# OBI_SlaveBoard_rev3.net
KiCad netlist of a schematic drawn in EAGLE
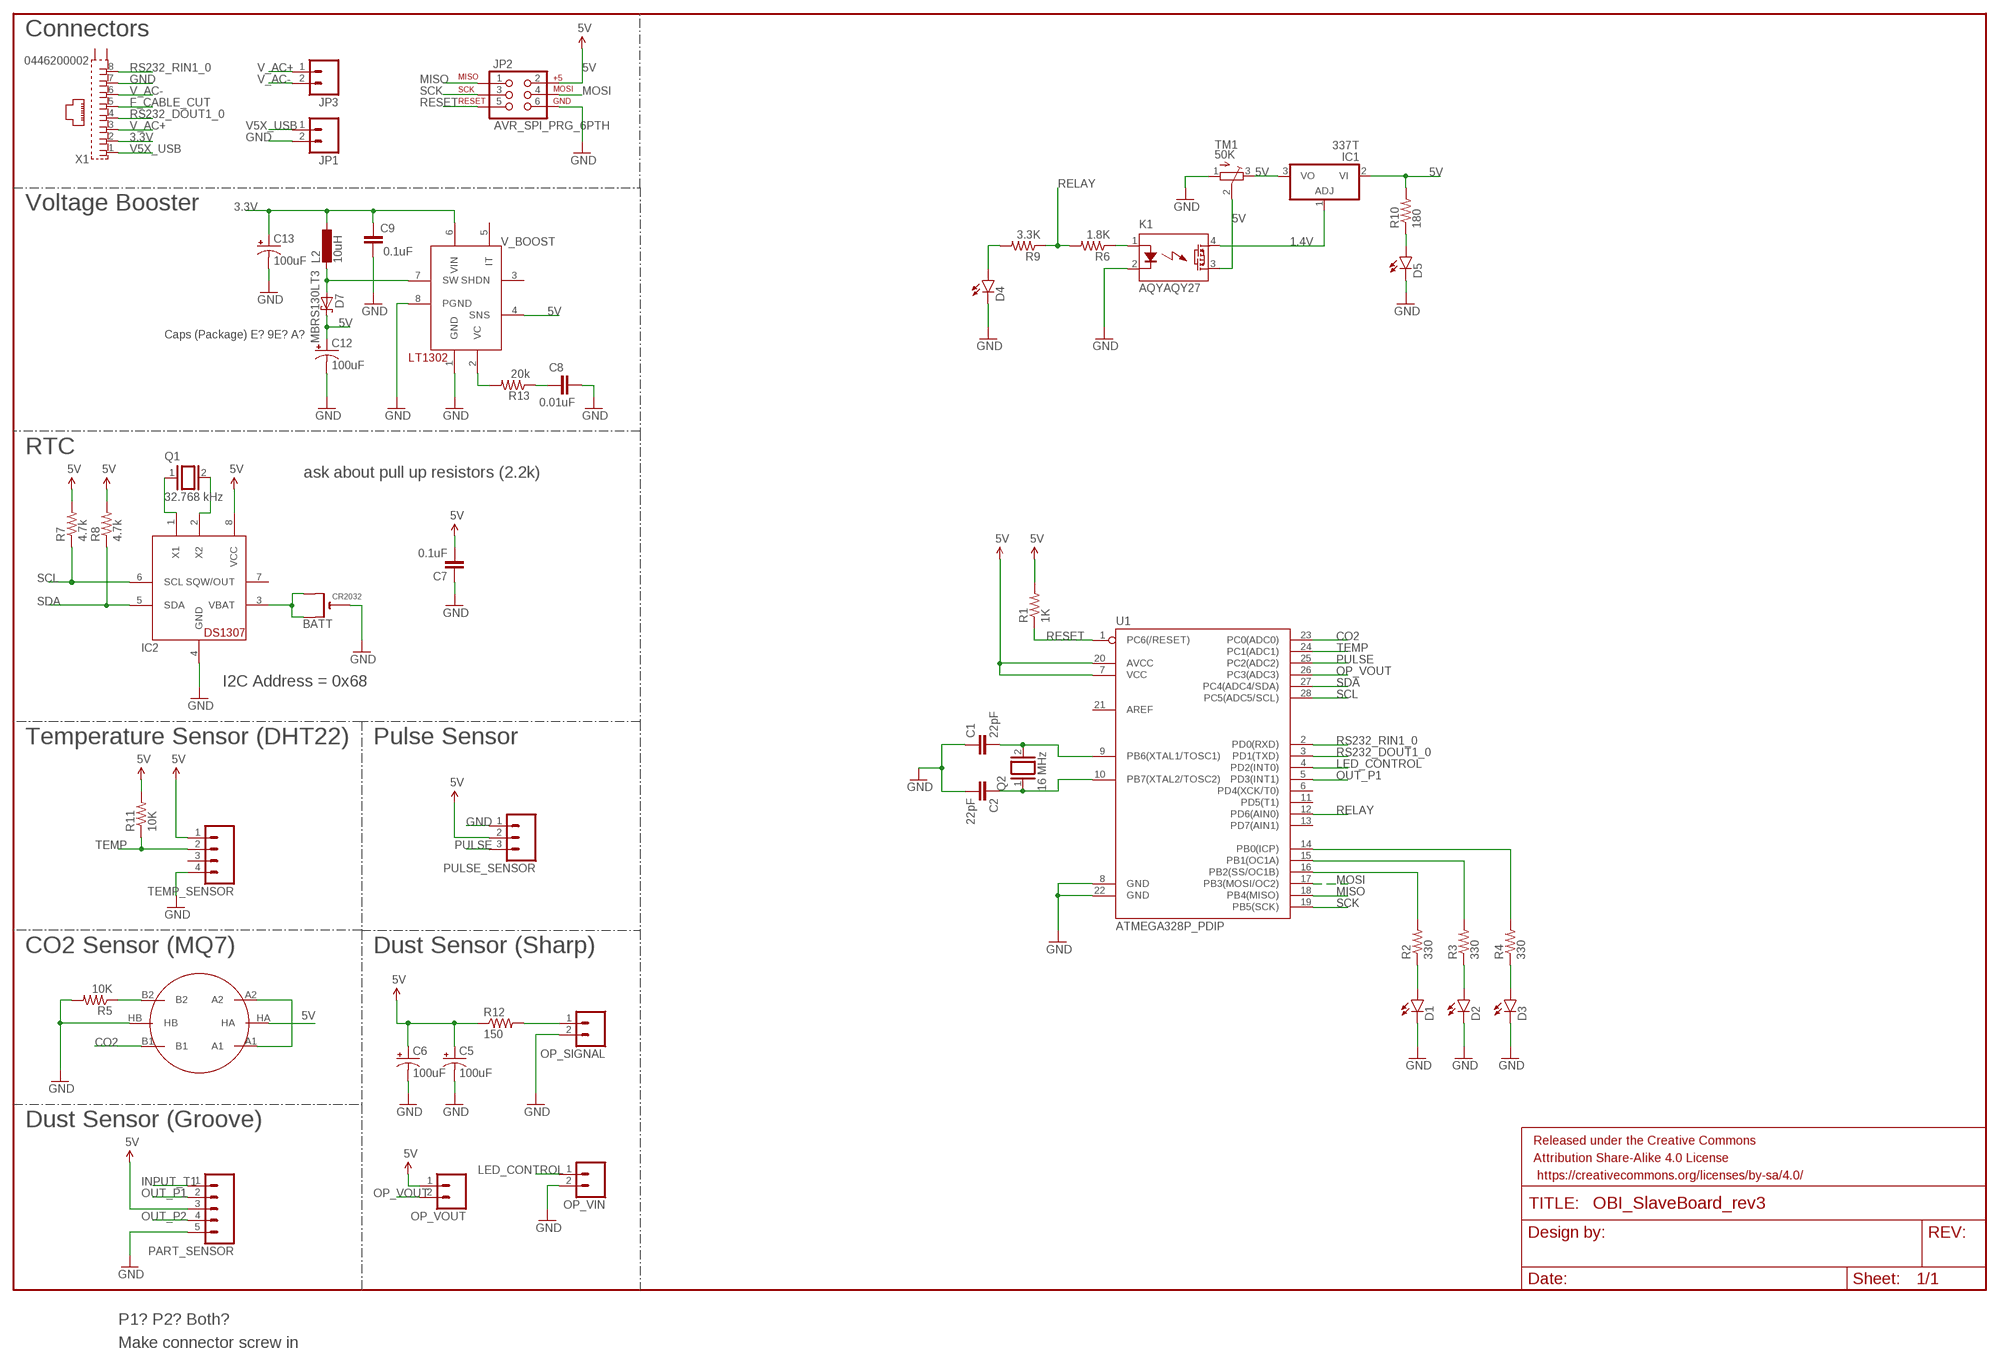
[diagram p0: schematic, sheet 1]

(export (version "E")
  (design (tool "Eeschema 10.0.6"))
  (components
    (comp (ref "BATT")
      (value "CR2032THM")
      (footprint "eagle-import:CR2032-THRU")
      (libsource (lib "eagle-import") (part "CR2032THM"))
    )
    (comp (ref "C1")
      (value "22pF")
      (footprint "eagle-import:CAP-PTH-SMALL-KIT")
      (libsource (lib "eagle-import") (part "CAPKIT"))
    )
    (comp (ref "C2")
      (value "22pF")
      (footprint "eagle-import:CAP-PTH-SMALL-KIT")
      (libsource (lib "eagle-import") (part "CAPKIT"))
    )
    (comp (ref "C5")
      (value "100uF")
      (footprint "eagle-import:CPOL-RADIAL-10UF-25V")
      (libsource (lib "eagle-import") (part "CAP_POLPTH2"))
    )
    (comp (ref "C6")
      (value "100uF")
      (footprint "eagle-import:CPOL-RADIAL-10UF-25V")
      (libsource (lib "eagle-import") (part "CAP_POLPTH2"))
    )
    (comp (ref "C7")
      (value "0.1uF")
      (footprint "eagle-import:CAP-PTH-SMALL-KIT")
      (libsource (lib "eagle-import") (part "CAPKIT"))
    )
    (comp (ref "C8")
      (value "0.01uF")
      (footprint "eagle-import:CAP-PTH-SMALL-KIT")
      (libsource (lib "eagle-import") (part "CAPKIT"))
    )
    (comp (ref "C9")
      (value "0.1uF")
      (footprint "eagle-import:CAP-PTH-SMALL-KIT")
      (libsource (lib "eagle-import") (part "CAPKIT"))
    )
    (comp (ref "C12")
      (value "100uF")
      (footprint "eagle-import:SANYO-OSCON_9E")
      (libsource (lib "eagle-import") (part "CPOL-USSANYO_9E"))
    )
    (comp (ref "C13")
      (value "100uF")
      (footprint "eagle-import:SANYO-OSCON_9E")
      (libsource (lib "eagle-import") (part "CPOL-USSANYO_9E"))
    )
    (comp (ref "CO2_SENSOR")
      (value "METHANE_SENSOR")
      (footprint "eagle-import:MQ-3")
      (libsource (lib "eagle-import") (part "METHANE_SENSOR"))
    )
    (comp (ref "D1")
      (value "LED5MM")
      (footprint "eagle-import:LED5MM")
      (libsource (lib "eagle-import") (part "LED5MM"))
    )
    (comp (ref "D2")
      (value "LED5MM")
      (footprint "eagle-import:LED5MM")
      (libsource (lib "eagle-import") (part "LED5MM"))
    )
    (comp (ref "D3")
      (value "LED5MM")
      (footprint "eagle-import:LED5MM")
      (libsource (lib "eagle-import") (part "LED5MM"))
    )
    (comp (ref "D4")
      (value "LED5MM")
      (footprint "eagle-import:LED5MM")
      (libsource (lib "eagle-import") (part "LED5MM"))
    )
    (comp (ref "D5")
      (value "LED5MM")
      (footprint "eagle-import:LED5MM")
      (libsource (lib "eagle-import") (part "LED5MM"))
    )
    (comp (ref "D7")
      (value "MBRS130LT3")
      (footprint "eagle-import:SMB")
      (libsource (lib "eagle-import") (part "MBRS130LT3"))
    )
    (comp (ref "FRAME1")
      (value "FRAME-LEDGER")
      (footprint "eagle-import:CREATIVE_COMMONS")
      (libsource (lib "eagle-import") (part "FRAME-LEDGER"))
    )
    (comp (ref "IC1")
      (value "337T")
      (footprint "eagle-import:TO220H")
      (libsource (lib "eagle-import") (part "337T"))
    )
    (comp (ref "IC2")
      (value "DS1307")
      (footprint "eagle-import:DIL08")
      (libsource (lib "eagle-import") (part "DS1307"))
    )
    (comp (ref "JP1")
      (value "M023.5MM")
      (footprint "eagle-import:SCREWTERMINAL-3.5MM-2")
      (libsource (lib "eagle-import") (part "M023.5MM"))
    )
    (comp (ref "JP2")
      (value "AVR_SPI_PRG_6PTH")
      (footprint "eagle-import:2X3")
      (libsource (lib "eagle-import") (part "AVR_SPI_PRG_6PTH"))
    )
    (comp (ref "JP3")
      (value "M023.5MM")
      (footprint "eagle-import:SCREWTERMINAL-3.5MM-2")
      (libsource (lib "eagle-import") (part "M023.5MM"))
    )
    (comp (ref "K1")
      (value "AQYAQY27")
      (footprint "eagle-import:AQY27")
      (libsource (lib "eagle-import") (part "AQYAQY27"))
    )
    (comp (ref "L2")
      (value "10uH")
      (footprint "eagle-import:DO3316P")
      (libsource (lib "eagle-import") (part "DO3316P"))
    )
    (comp (ref "OP_SIGNAL")
      (value "M023.5MM")
      (footprint "eagle-import:SCREWTERMINAL-3.5MM-2")
      (libsource (lib "eagle-import") (part "M023.5MM"))
    )
    (comp (ref "OP_VIN")
      (value "M023.5MM")
      (footprint "eagle-import:SCREWTERMINAL-3.5MM-2")
      (libsource (lib "eagle-import") (part "M023.5MM"))
    )
    (comp (ref "OP_VOUT")
      (value "M023.5MM")
      (footprint "eagle-import:SCREWTERMINAL-3.5MM-2")
      (libsource (lib "eagle-import") (part "M023.5MM"))
    )
    (comp (ref "PART_SENSOR")
      (value "M05JST")
      (footprint "eagle-import:JST-5-PTH")
      (libsource (lib "eagle-import") (part "M05JST"))
    )
    (comp (ref "PULSE_SENSOR")
      (value "M03-SCREW-5MM")
      (footprint "eagle-import:SCREWTERMINAL-5MM-3")
      (libsource (lib "eagle-import") (part "M03-SCREW-5MM"))
    )
    (comp (ref "Q1")
      (value "32.768 kHz")
      (footprint "eagle-import:QS")
      (libsource (lib "eagle-import") (part "XTAL/S"))
    )
    (comp (ref "Q2")
      (value "16 MHz")
      (footprint "eagle-import:QS")
      (libsource (lib "eagle-import") (part "XTAL/S"))
    )
    (comp (ref "R1")
      (value "1K")
      (footprint "eagle-import:AXIAL-0.4")
      (libsource (lib "eagle-import") (part "RESISTORPTH-1/4W"))
    )
    (comp (ref "R2")
      (value "330")
      (footprint "eagle-import:AXIAL-0.4")
      (libsource (lib "eagle-import") (part "SparkFun-Resistors_RESISTORPTH-1/4W"))
    )
    (comp (ref "R3")
      (value "330")
      (footprint "eagle-import:AXIAL-0.4")
      (libsource (lib "eagle-import") (part "SparkFun-Resistors_RESISTORPTH-1/4W"))
    )
    (comp (ref "R4")
      (value "330")
      (footprint "eagle-import:AXIAL-0.4")
      (libsource (lib "eagle-import") (part "SparkFun-Resistors_RESISTORPTH-1/4W"))
    )
    (comp (ref "R5")
      (value "10K")
      (footprint "eagle-import:AXIAL-0.4")
      (libsource (lib "eagle-import") (part "RESISTORPTH-1/4W"))
    )
    (comp (ref "R6")
      (value "1.8K")
      (footprint "eagle-import:AXIAL-0.4")
      (libsource (lib "eagle-import") (part "RESISTORPTH-1/4W"))
    )
    (comp (ref "R7")
      (value "4.7k")
      (footprint "eagle-import:AXIAL-0.4")
      (libsource (lib "eagle-import") (part "RESISTORPTH-1/4W"))
    )
    (comp (ref "R8")
      (value "4.7k")
      (footprint "eagle-import:AXIAL-0.4")
      (libsource (lib "eagle-import") (part "RESISTORPTH-1/4W"))
    )
    (comp (ref "R9")
      (value "3.3K")
      (footprint "eagle-import:AXIAL-0.4")
      (libsource (lib "eagle-import") (part "RESISTORPTH-1/4W"))
    )
    (comp (ref "R10")
      (value "180")
      (footprint "eagle-import:AXIAL-0.4")
      (libsource (lib "eagle-import") (part "SparkFun-Resistors_RESISTORPTH-1/4W"))
    )
    (comp (ref "R11")
      (value "10K")
      (footprint "eagle-import:AXIAL-0.4")
      (libsource (lib "eagle-import") (part "SparkFun-Resistors_RESISTORPTH-1/4W"))
    )
    (comp (ref "R12")
      (value "150")
      (footprint "eagle-import:AXIAL-0.4")
      (libsource (lib "eagle-import") (part "SparkFun-Resistors_RESISTORPTH-1/4W"))
    )
    (comp (ref "R13")
      (value "20k")
      (footprint "eagle-import:AXIAL-0.4")
      (libsource (lib "eagle-import") (part "SparkFun-Resistors_RESISTORPTH-1/4W"))
    )
    (comp (ref "TEMP_SENSOR")
      (value "M04SCREW")
      (footprint "eagle-import:SCREWTERMINAL-3.5MM-4")
      (libsource (lib "eagle-import") (part "M04SCREW"))
    )
    (comp (ref "TM1")
      (value "50K")
      (footprint "eagle-import:TC33X")
      (libsource (lib "eagle-import") (part "TRIMPOTTC33X"))
    )
    (comp (ref "U1")
      (value "ATMEGA328P_PDIP")
      (footprint "eagle-import:DIL28-3")
      (libsource (lib "eagle-import") (part "ATMEGA328P_PDIP"))
    )
    (comp (ref "V_BOOST")
      (value "LT1302")
      (footprint "eagle-import:DIL08")
      (libsource (lib "eagle-import") (part "LT1302"))
    )
    (comp (ref "X1")
      (value "0446200002")
      (footprint "eagle-import:0446200002")
      (fields (field (name "MF") "MOLEX"))
      (libsource (lib "eagle-import") (part "0446200002"))
    )
  )
  (nets
    (net (code "1") (name "/1.4V") (class "Default")
      (node (ref "IC1") (pin "1") (pinfunction "ADJ_1") (pintype "input"))
      (node (ref "K1") (pin "4") (pinfunction "DS1_4") (pintype "passive"))
    )
    (net (code "2") (name "/3.3V") (class "Default")
      (node (ref "C13") (pin "+") (pinfunction "+_+") (pintype "passive"))
      (node (ref "C9") (pin "1") (pinfunction "1_1") (pintype "passive"))
      (node (ref "L2") (pin "2") (pinfunction "2_2") (pintype "passive"))
      (node (ref "V_BOOST") (pin "6") (pinfunction "VIN_6") (pintype "input"))
      (node (ref "X1") (pin "2") (pinfunction "2_2") (pintype "passive"))
    )
    (net (code "3") (name "/CO2") (class "Default")
      (node (ref "CO2_SENSOR") (pin "B1") (pinfunction "B1_B1") (pintype "bidirectional"))
      (node (ref "U1") (pin "23") (pinfunction "PC0(ADC0)_23") (pintype "bidirectional"))
    )
    (net (code "4") (name "/F_CABLE_CUT") (class "Default")
      (node (ref "X1") (pin "5") (pinfunction "5_5") (pintype "passive"))
    )
    (net (code "5") (name "/INPUT_T1") (class "Default")
      (node (ref "PART_SENSOR") (pin "1") (pinfunction "1_1") (pintype "passive"))
    )
    (net (code "6") (name "/LED_CONTROL") (class "Default")
      (node (ref "OP_VIN") (pin "1") (pinfunction "1_1") (pintype "passive"))
      (node (ref "U1") (pin "4") (pinfunction "PD2(INT0)_4") (pintype "bidirectional"))
    )
    (net (code "7") (name "/MISO") (class "Default")
      (node (ref "JP2") (pin "1") (pinfunction "1_1") (pintype "passive"))
      (node (ref "U1") (pin "18") (pinfunction "PB4(MISO)_18") (pintype "bidirectional"))
    )
    (net (code "8") (name "/MOSI") (class "Default")
      (node (ref "JP2") (pin "4") (pinfunction "4_4") (pintype "passive"))
      (node (ref "U1") (pin "17") (pinfunction "PB3(MOSI/OC2)_17") (pintype "bidirectional"))
    )
    (net (code "9") (name "/OP_VOUT") (class "Default")
      (node (ref "OP_VOUT") (pin "2") (pinfunction "2_2") (pintype "passive"))
      (node (ref "U1") (pin "26") (pinfunction "PC3(ADC3)_26") (pintype "bidirectional"))
    )
    (net (code "10") (name "/OUT_P1") (class "Default")
      (node (ref "PART_SENSOR") (pin "2") (pinfunction "2_2") (pintype "passive"))
      (node (ref "U1") (pin "5") (pinfunction "PD3(INT1)_5") (pintype "bidirectional"))
    )
    (net (code "11") (name "/OUT_P2") (class "Default")
      (node (ref "PART_SENSOR") (pin "4") (pinfunction "4_4") (pintype "passive"))
    )
    (net (code "12") (name "/PULSE") (class "Default")
      (node (ref "PULSE_SENSOR") (pin "3") (pinfunction "3_3") (pintype "passive"))
      (node (ref "U1") (pin "25") (pinfunction "PC2(ADC2)_25") (pintype "bidirectional"))
    )
    (net (code "13") (name "/RELAY") (class "Default")
      (node (ref "R6") (pin "P$2") (pinfunction "2_P$2") (pintype "passive"))
      (node (ref "R9") (pin "P$1") (pinfunction "1_P$1") (pintype "passive"))
      (node (ref "U1") (pin "12") (pinfunction "PD6(AIN0)_12") (pintype "bidirectional"))
    )
    (net (code "14") (name "/RESET") (class "Default")
      (node (ref "JP2") (pin "5") (pinfunction "5_5") (pintype "passive"))
      (node (ref "R1") (pin "P$1") (pinfunction "1_P$1") (pintype "passive"))
      (node (ref "U1") (pin "1") (pinfunction "PC6(/RESET)_1") (pintype "bidirectional"))
    )
    (net (code "15") (name "/RS232_DOUT1_0") (class "Default")
      (node (ref "U1") (pin "3") (pinfunction "PD1(TXD)_3") (pintype "bidirectional"))
      (node (ref "X1") (pin "4") (pinfunction "4_4") (pintype "passive"))
    )
    (net (code "16") (name "/RS232_RIN1_0") (class "Default")
      (node (ref "U1") (pin "2") (pinfunction "PD0(RXD)_2") (pintype "bidirectional"))
      (node (ref "X1") (pin "8") (pinfunction "8_8") (pintype "passive"))
    )
    (net (code "17") (name "/SCK") (class "Default")
      (node (ref "JP2") (pin "3") (pinfunction "3_3") (pintype "passive"))
      (node (ref "U1") (pin "19") (pinfunction "PB5(SCK)_19") (pintype "bidirectional"))
    )
    (net (code "18") (name "/SCL") (class "Default")
      (node (ref "IC2") (pin "6") (pinfunction "SCL_6") (pintype "bidirectional"))
      (node (ref "R7") (pin "P$1") (pinfunction "1_P$1") (pintype "passive"))
      (node (ref "U1") (pin "28") (pinfunction "PC5(ADC5/SCL)_28") (pintype "bidirectional"))
    )
    (net (code "19") (name "/SDA") (class "Default")
      (node (ref "IC2") (pin "5") (pinfunction "SDA_5") (pintype "bidirectional"))
      (node (ref "R8") (pin "P$1") (pinfunction "1_P$1") (pintype "passive"))
      (node (ref "U1") (pin "27") (pinfunction "PC4(ADC4/SDA)_27") (pintype "bidirectional"))
    )
    (net (code "20") (name "/TEMP") (class "Default")
      (node (ref "R11") (pin "P$1") (pinfunction "1_P$1") (pintype "passive"))
      (node (ref "TEMP_SENSOR") (pin "2") (pinfunction "2_2") (pintype "passive"))
      (node (ref "U1") (pin "24") (pinfunction "PC1(ADC1)_24") (pintype "bidirectional"))
    )
    (net (code "21") (name "/V5X_USB") (class "Default")
      (node (ref "JP1") (pin "1") (pinfunction "1_1") (pintype "passive"))
      (node (ref "X1") (pin "1") (pinfunction "1_1") (pintype "passive"))
    )
    (net (code "22") (name "/V_AC+") (class "Default")
      (node (ref "JP3") (pin "1") (pinfunction "1_1") (pintype "passive"))
      (node (ref "X1") (pin "3") (pinfunction "3_3") (pintype "passive"))
    )
    (net (code "23") (name "/V_AC-") (class "Default")
      (node (ref "JP3") (pin "2") (pinfunction "2_2") (pintype "passive"))
      (node (ref "X1") (pin "6") (pinfunction "6_6") (pintype "passive"))
    )
    (net (code "24") (name "5V") (class "Default")
      (node (ref "C12") (pin "+") (pinfunction "+_+") (pintype "passive"))
      (node (ref "C5") (pin "1") (pinfunction "+_1") (pintype "passive"))
      (node (ref "C6") (pin "1") (pinfunction "+_1") (pintype "passive"))
      (node (ref "C7") (pin "2") (pinfunction "2_2") (pintype "passive"))
      (node (ref "CO2_SENSOR") (pin "HA") (pinfunction "HA_HA") (pintype "bidirectional"))
      (node (ref "D7") (pin "C") (pinfunction "C_C") (pintype "passive"))
      (node (ref "IC1") (pin "2") (pinfunction "VI_2") (pintype "input"))
      (node (ref "IC1") (pin "3") (pinfunction "VO_3") (pintype "passive"))
      (node (ref "IC2") (pin "8") (pinfunction "VCC_8") (pintype "power_in"))
      (node (ref "JP2") (pin "2") (pinfunction "2_2") (pintype "passive"))
      (node (ref "K1") (pin "3") (pinfunction "DS2_3") (pintype "passive"))
      (node (ref "OP_VOUT") (pin "1") (pinfunction "1_1") (pintype "passive"))
      (node (ref "PART_SENSOR") (pin "3") (pinfunction "3_3") (pintype "passive"))
      (node (ref "PULSE_SENSOR") (pin "2") (pinfunction "2_2") (pintype "passive"))
      (node (ref "R1") (pin "P$2") (pinfunction "2_P$2") (pintype "passive"))
      (node (ref "R10") (pin "P$2") (pinfunction "2_P$2") (pintype "passive"))
      (node (ref "R11") (pin "P$2") (pinfunction "2_P$2") (pintype "passive"))
      (node (ref "R12") (pin "P$1") (pinfunction "1_P$1") (pintype "passive"))
      (node (ref "R7") (pin "P$2") (pinfunction "2_P$2") (pintype "passive"))
      (node (ref "R8") (pin "P$2") (pinfunction "2_P$2") (pintype "passive"))
      (node (ref "TEMP_SENSOR") (pin "1") (pinfunction "1_1") (pintype "passive"))
      (node (ref "TM1") (pin "2") (pinfunction "S_2") (pintype "passive"))
      (node (ref "TM1") (pin "3") (pinfunction "E_3") (pintype "passive"))
      (node (ref "U1") (pin "20") (pinfunction "AVCC_20") (pintype "bidirectional"))
      (node (ref "U1") (pin "7") (pinfunction "VCC_7") (pintype "bidirectional"))
      (node (ref "V_BOOST") (pin "4") (pinfunction "SNS_4") (pintype "passive"))
    )
    (net (code "25") (name "GND") (class "Default")
      (node (ref "BATT") (pin "-") (pinfunction "-_-") (pintype "passive"))
      (node (ref "C1") (pin "1") (pinfunction "1_1") (pintype "passive"))
      (node (ref "C12") (pin "-") (pinfunction "-_-") (pintype "passive"))
      (node (ref "C13") (pin "-") (pinfunction "-_-") (pintype "passive"))
      (node (ref "C2") (pin "2") (pinfunction "2_2") (pintype "passive"))
      (node (ref "C5") (pin "2") (pinfunction "-_2") (pintype "passive"))
      (node (ref "C6") (pin "2") (pinfunction "-_2") (pintype "passive"))
      (node (ref "C7") (pin "1") (pinfunction "1_1") (pintype "passive"))
      (node (ref "C8") (pin "1") (pinfunction "1_1") (pintype "passive"))
      (node (ref "C9") (pin "2") (pinfunction "2_2") (pintype "passive"))
      (node (ref "CO2_SENSOR") (pin "HB") (pinfunction "HB_HB") (pintype "bidirectional"))
      (node (ref "D1") (pin "K") (pinfunction "C_K") (pintype "passive"))
      (node (ref "D2") (pin "K") (pinfunction "C_K") (pintype "passive"))
      (node (ref "D3") (pin "K") (pinfunction "C_K") (pintype "passive"))
      (node (ref "D4") (pin "K") (pinfunction "C_K") (pintype "passive"))
      (node (ref "D5") (pin "K") (pinfunction "C_K") (pintype "passive"))
      (node (ref "IC2") (pin "4") (pinfunction "GND_4") (pintype "power_in"))
      (node (ref "JP1") (pin "2") (pinfunction "2_2") (pintype "passive"))
      (node (ref "JP2") (pin "6") (pinfunction "6_6") (pintype "passive"))
      (node (ref "K1") (pin "2") (pinfunction "K_2") (pintype "passive"))
      (node (ref "OP_SIGNAL") (pin "2") (pinfunction "2_2") (pintype "passive"))
      (node (ref "OP_VIN") (pin "2") (pinfunction "2_2") (pintype "passive"))
      (node (ref "PART_SENSOR") (pin "5") (pinfunction "5_5") (pintype "passive"))
      (node (ref "PULSE_SENSOR") (pin "1") (pinfunction "1_1") (pintype "passive"))
      (node (ref "R5") (pin "P$2") (pinfunction "2_P$2") (pintype "passive"))
      (node (ref "TEMP_SENSOR") (pin "4") (pinfunction "4_4") (pintype "passive"))
      (node (ref "TM1") (pin "1") (pinfunction "A_1") (pintype "passive"))
      (node (ref "U1") (pin "22") (pinfunction "GND_22") (pintype "bidirectional"))
      (node (ref "U1") (pin "8") (pinfunction "GND_8") (pintype "bidirectional"))
      (node (ref "V_BOOST") (pin "1") (pinfunction "GND_1") (pintype "input"))
      (node (ref "V_BOOST") (pin "8") (pinfunction "PGND_8") (pintype "input"))
      (node (ref "X1") (pin "7") (pinfunction "7_7") (pintype "passive"))
    )
    (net (code "26") (name "Net-(BATT-+)") (class "Default")
      (node (ref "BATT") (pin "+1") (pinfunction "+_+1") (pintype "passive"))
      (node (ref "BATT") (pin "+2") (pinfunction "+1_+2") (pintype "passive"))
      (node (ref "IC2") (pin "3") (pinfunction "VBAT_3") (pintype "power_in"))
    )
    (net (code "27") (name "Net-(CO2_SENSOR-PadA1)") (class "Default")
      (node (ref "CO2_SENSOR") (pin "A1") (pinfunction "A1_A1") (pintype "bidirectional"))
      (node (ref "CO2_SENSOR") (pin "A2") (pinfunction "A2_A2") (pintype "bidirectional"))
    )
    (net (code "28") (name "Net-(IC2-X1)") (class "Default")
      (node (ref "IC2") (pin "1") (pinfunction "X1_1") (pintype "passive"))
      (node (ref "Q1") (pin "1") (pinfunction "1_1") (pintype "passive"))
    )
    (net (code "29") (name "Net-(IC2-X2)") (class "Default")
      (node (ref "IC2") (pin "2") (pinfunction "X2_2") (pintype "passive"))
      (node (ref "Q1") (pin "2") (pinfunction "2_2") (pintype "passive"))
    )
    (net (code "30") (name "Net-(K1-A)") (class "Default")
      (node (ref "K1") (pin "1") (pinfunction "A_1") (pintype "passive"))
      (node (ref "R6") (pin "P$1") (pinfunction "1_P$1") (pintype "passive"))
    )
    (net (code "31") (name "Net-(R2-1)") (class "Default")
      (node (ref "D1") (pin "A") (pinfunction "A_A") (pintype "passive"))
      (node (ref "R2") (pin "P$1") (pinfunction "1_P$1") (pintype "passive"))
    )
    (net (code "32") (name "Net-(R2-2)") (class "Default")
      (node (ref "R2") (pin "P$2") (pinfunction "2_P$2") (pintype "passive"))
      (node (ref "U1") (pin "16") (pinfunction "PB2(SS/OC1B)_16") (pintype "bidirectional"))
    )
    (net (code "33") (name "Net-(R3-1)") (class "Default")
      (node (ref "D2") (pin "A") (pinfunction "A_A") (pintype "passive"))
      (node (ref "R3") (pin "P$1") (pinfunction "1_P$1") (pintype "passive"))
    )
    (net (code "34") (name "Net-(R3-2)") (class "Default")
      (node (ref "R3") (pin "P$2") (pinfunction "2_P$2") (pintype "passive"))
      (node (ref "U1") (pin "15") (pinfunction "PB1(OC1A)_15") (pintype "bidirectional"))
    )
    (net (code "35") (name "Net-(R4-1)") (class "Default")
      (node (ref "D3") (pin "A") (pinfunction "A_A") (pintype "passive"))
      (node (ref "R4") (pin "P$1") (pinfunction "1_P$1") (pintype "passive"))
    )
    (net (code "36") (name "Net-(R4-2)") (class "Default")
      (node (ref "R4") (pin "P$2") (pinfunction "2_P$2") (pintype "passive"))
      (node (ref "U1") (pin "14") (pinfunction "PB0(ICP)_14") (pintype "bidirectional"))
    )
    (net (code "37") (name "Net-(R5-1)") (class "Default")
      (node (ref "CO2_SENSOR") (pin "B2") (pinfunction "B2_B2") (pintype "bidirectional"))
      (node (ref "R5") (pin "P$1") (pinfunction "1_P$1") (pintype "passive"))
    )
    (net (code "38") (name "Net-(R9-2)") (class "Default")
      (node (ref "D4") (pin "A") (pinfunction "A_A") (pintype "passive"))
      (node (ref "R9") (pin "P$2") (pinfunction "2_P$2") (pintype "passive"))
    )
    (net (code "39") (name "Net-(R10-1)") (class "Default")
      (node (ref "D5") (pin "A") (pinfunction "A_A") (pintype "passive"))
      (node (ref "R10") (pin "P$1") (pinfunction "1_P$1") (pintype "passive"))
    )
    (net (code "40") (name "Net-(R12-2)") (class "Default")
      (node (ref "OP_SIGNAL") (pin "1") (pinfunction "1_1") (pintype "passive"))
      (node (ref "R12") (pin "P$2") (pinfunction "2_P$2") (pintype "passive"))
    )
    (net (code "41") (name "Net-(R13-1)") (class "Default")
      (node (ref "C8") (pin "2") (pinfunction "2_2") (pintype "passive"))
      (node (ref "R13") (pin "P$1") (pinfunction "1_P$1") (pintype "passive"))
    )
    (net (code "42") (name "Net-(R13-2)") (class "Default")
      (node (ref "R13") (pin "P$2") (pinfunction "2_P$2") (pintype "passive"))
      (node (ref "V_BOOST") (pin "2") (pinfunction "VC_2") (pintype "passive"))
    )
    (net (code "43") (name "Net-(U1-PB6(XTAL1{slash}TOSC1))") (class "Default")
      (node (ref "C1") (pin "2") (pinfunction "2_2") (pintype "passive"))
      (node (ref "Q2") (pin "2") (pinfunction "2_2") (pintype "passive"))
      (node (ref "U1") (pin "9") (pinfunction "PB6(XTAL1/TOSC1)_9") (pintype "bidirectional"))
    )
    (net (code "44") (name "Net-(U1-PB7(XTAL2{slash}TOSC2))") (class "Default")
      (node (ref "C2") (pin "1") (pinfunction "1_1") (pintype "passive"))
      (node (ref "Q2") (pin "1") (pinfunction "1_1") (pintype "passive"))
      (node (ref "U1") (pin "10") (pinfunction "PB7(XTAL2/TOSC2)_10") (pintype "bidirectional"))
    )
    (net (code "45") (name "Net-(V_BOOST-SW)") (class "Default")
      (node (ref "D7") (pin "A") (pinfunction "A_A") (pintype "passive"))
      (node (ref "L2") (pin "1") (pinfunction "1_1") (pintype "passive"))
      (node (ref "V_BOOST") (pin "7") (pinfunction "SW_7") (pintype "input"))
    )
    (net (code "46") (name "unconnected-(IC2-SQW{slash}OUT-Pad7)") (class "Default")
      (node (ref "IC2") (pin "7") (pinfunction "SQW/OUT_7") (pintype "bidirectional"))
    )
    (net (code "47") (name "unconnected-(TEMP_SENSOR-Pad3)") (class "Default")
      (node (ref "TEMP_SENSOR") (pin "3") (pinfunction "3_3") (pintype "passive"))
    )
    (net (code "48") (name "unconnected-(U1-AREF-Pad21)") (class "Default")
      (node (ref "U1") (pin "21") (pinfunction "AREF_21") (pintype "bidirectional"))
    )
    (net (code "49") (name "unconnected-(U1-PD4(XCK{slash}T0)-Pad6)") (class "Default")
      (node (ref "U1") (pin "6") (pinfunction "PD4(XCK/T0)_6") (pintype "bidirectional"))
    )
    (net (code "50") (name "unconnected-(U1-PD5(T1)-Pad11)") (class "Default")
      (node (ref "U1") (pin "11") (pinfunction "PD5(T1)_11") (pintype "bidirectional"))
    )
    (net (code "51") (name "unconnected-(U1-PD7(AIN1)-Pad13)") (class "Default")
      (node (ref "U1") (pin "13") (pinfunction "PD7(AIN1)_13") (pintype "bidirectional"))
    )
    (net (code "52") (name "unconnected-(V_BOOST-IT-Pad5)") (class "Default")
      (node (ref "V_BOOST") (pin "5") (pinfunction "IT_5") (pintype "input"))
    )
    (net (code "53") (name "unconnected-(V_BOOST-SHDN-Pad3)") (class "Default")
      (node (ref "V_BOOST") (pin "3") (pinfunction "SHDN_3") (pintype "input"))
    )
    (net (code "54") (name "unconnected-(X1-S1-PadS@1)") (class "Default")
      (node (ref "X1") (pin "S@1") (pinfunction "S1_S@1") (pintype "passive"))
    )
    (net (code "55") (name "unconnected-(X1-S2-PadS@2)") (class "Default")
      (node (ref "X1") (pin "S@2") (pinfunction "S2_S@2") (pintype "passive"))
    )
  )
)
